# IREC-Sensor-PCB.net
KiCad netlist of a schematic drawn in EAGLE
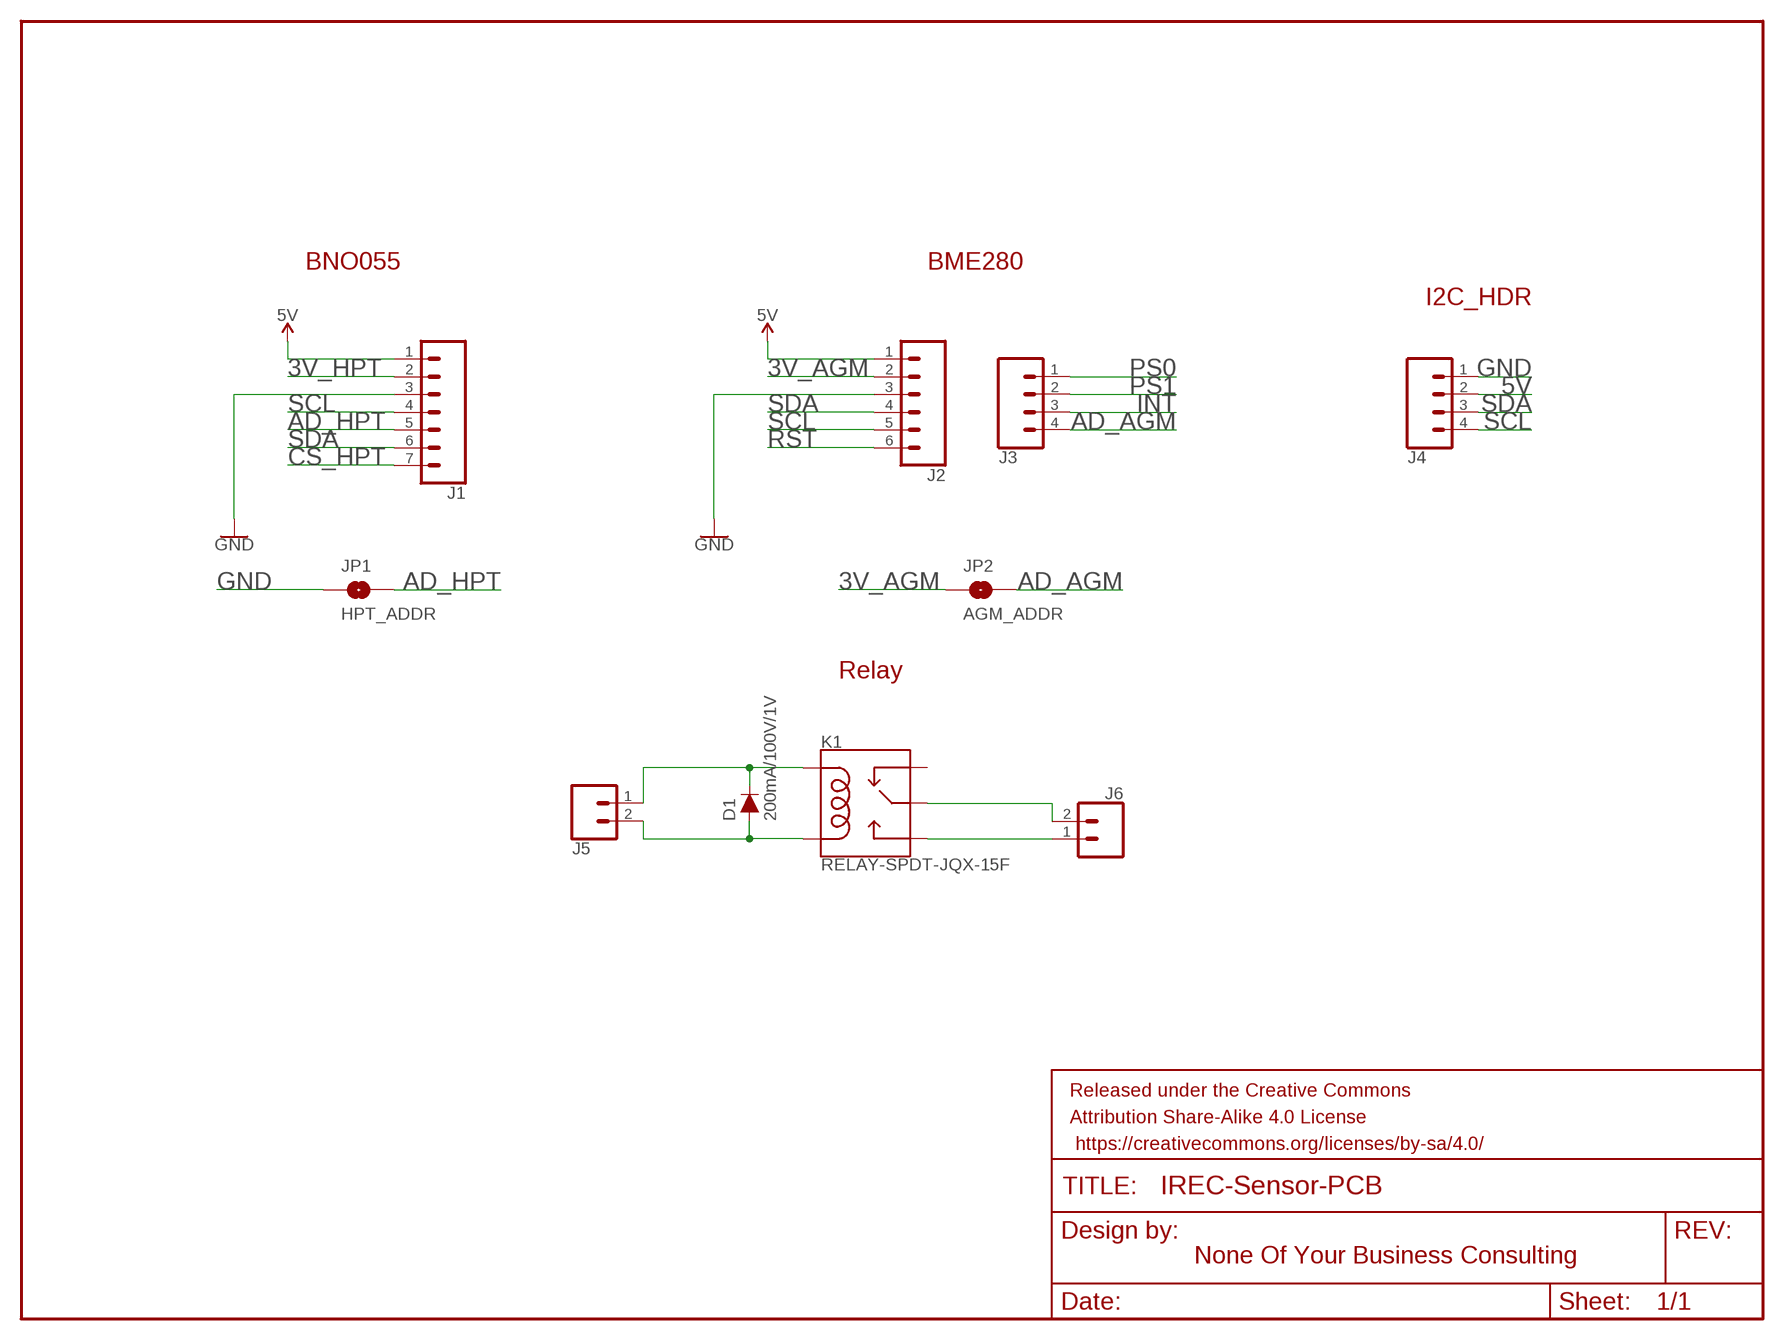
[diagram p0: schematic, sheet 1]

(export (version "E")
  (design (tool "Eeschema 10.0.6"))
  (components
    (comp (ref "D1")
      (value "200mA/100V/1V")
      (footprint "eagle-import:DIODE-1N4148")
      (libsource (lib "eagle-import") (part "DIODE-1N4148"))
    )
    (comp (ref "FRAME1")
      (value "FRAME-LETTER")
      (footprint "eagle-import:CREATIVE_COMMONS")
      (libsource (lib "eagle-import") (part "FRAME-LETTER"))
    )
    (comp (ref "J1")
      (value "CONN_07")
      (footprint "eagle-import:1X07")
      (libsource (lib "eagle-import") (part "CONN_07"))
    )
    (comp (ref "J2")
      (value "CONN_06SILK_FEMALE_PTH")
      (footprint "eagle-import:1X06")
      (libsource (lib "eagle-import") (part "CONN_06SILK_FEMALE_PTH"))
    )
    (comp (ref "J3")
      (value "CONN_04")
      (footprint "eagle-import:1X04")
      (libsource (lib "eagle-import") (part "CONN_04"))
    )
    (comp (ref "J4")
      (value "CONN_04SCREW")
      (footprint "eagle-import:SCREWTERMINAL-3.5MM-4")
      (libsource (lib "eagle-import") (part "CONN_04SCREW"))
    )
    (comp (ref "J5")
      (value "CONN_023.5MM")
      (footprint "eagle-import:SCREWTERMINAL-3.5MM-2")
      (libsource (lib "eagle-import") (part "CONN_023.5MM"))
    )
    (comp (ref "J6")
      (value "CONN_023.5MM")
      (footprint "eagle-import:SCREWTERMINAL-3.5MM-2")
      (libsource (lib "eagle-import") (part "CONN_023.5MM"))
    )
    (comp (ref "JP1")
      (value "HPT_ADDR")
      (footprint "eagle-import:SMT-JUMPER_2_NO_SILK")
      (libsource (lib "eagle-import") (part "JUMPER-SMT_2_NO_SILK"))
    )
    (comp (ref "JP2")
      (value "AGM_ADDR")
      (footprint "eagle-import:SMT-JUMPER_2_NO_SILK")
      (libsource (lib "eagle-import") (part "JUMPER-SMT_2_NO_SILK"))
    )
    (comp (ref "K1")
      (value "RELAY-SPDT-JQX-15F")
      (footprint "eagle-import:RELAY-T90")
      (libsource (lib "eagle-import") (part "RELAY-SPDT-JQX-15F"))
    )
  )
  (nets
    (net (code "1") (name "/3V_AGM") (class "Default")
      (node (ref "J2") (pin "2") (pinfunction "2_2") (pintype "passive"))
      (node (ref "JP2") (pin "1") (pinfunction "1_1") (pintype "passive"))
    )
    (net (code "2") (name "/3V_HPT") (class "Default")
      (node (ref "J1") (pin "2") (pinfunction "2_2") (pintype "passive"))
    )
    (net (code "3") (name "/AD_AGM") (class "Default")
      (node (ref "J3") (pin "4") (pinfunction "4_4") (pintype "passive"))
      (node (ref "JP2") (pin "2") (pinfunction "2_2") (pintype "passive"))
    )
    (net (code "4") (name "/AD_HPT") (class "Default")
      (node (ref "J1") (pin "5") (pinfunction "5_5") (pintype "passive"))
      (node (ref "JP1") (pin "2") (pinfunction "2_2") (pintype "passive"))
    )
    (net (code "5") (name "/CS_HPT") (class "Default")
      (node (ref "J1") (pin "7") (pinfunction "7_7") (pintype "passive"))
    )
    (net (code "6") (name "/INT") (class "Default")
      (node (ref "J3") (pin "3") (pinfunction "3_3") (pintype "passive"))
    )
    (net (code "7") (name "/PS0") (class "Default")
      (node (ref "J3") (pin "1") (pinfunction "1_1") (pintype "passive"))
    )
    (net (code "8") (name "/PS1") (class "Default")
      (node (ref "J3") (pin "2") (pinfunction "2_2") (pintype "passive"))
    )
    (net (code "9") (name "/RST") (class "Default")
      (node (ref "J2") (pin "6") (pinfunction "6_6") (pintype "passive"))
    )
    (net (code "10") (name "/SCL") (class "Default")
      (node (ref "J1") (pin "4") (pinfunction "4_4") (pintype "passive"))
      (node (ref "J2") (pin "5") (pinfunction "5_5") (pintype "passive"))
      (node (ref "J4") (pin "4") (pinfunction "4_4") (pintype "passive"))
    )
    (net (code "11") (name "/SDA") (class "Default")
      (node (ref "J1") (pin "6") (pinfunction "6_6") (pintype "passive"))
      (node (ref "J2") (pin "4") (pinfunction "4_4") (pintype "passive"))
      (node (ref "J4") (pin "3") (pinfunction "3_3") (pintype "passive"))
    )
    (net (code "12") (name "5V") (class "Default")
      (node (ref "J1") (pin "1") (pinfunction "1_1") (pintype "passive"))
      (node (ref "J2") (pin "1") (pinfunction "1_1") (pintype "passive"))
      (node (ref "J4") (pin "2") (pinfunction "2_2") (pintype "passive"))
    )
    (net (code "13") (name "GND") (class "Default")
      (node (ref "J1") (pin "3") (pinfunction "3_3") (pintype "passive"))
      (node (ref "J2") (pin "3") (pinfunction "3_3") (pintype "passive"))
      (node (ref "J4") (pin "1") (pinfunction "1_1") (pintype "passive"))
      (node (ref "JP1") (pin "1") (pinfunction "1_1") (pintype "passive"))
    )
    (net (code "14") (name "Net-(D1-PadA)") (class "Default")
      (node (ref "D1") (pin "A") (pinfunction "A_A") (pintype "passive"))
      (node (ref "J5") (pin "2") (pinfunction "2_2") (pintype "passive"))
      (node (ref "K1") (pin "COIL2") (pinfunction "COIL2_COIL2") (pintype "bidirectional"))
    )
    (net (code "15") (name "Net-(D1-PadC)") (class "Default")
      (node (ref "D1") (pin "C") (pinfunction "C_C") (pintype "passive"))
      (node (ref "J5") (pin "1") (pinfunction "1_1") (pintype "passive"))
      (node (ref "K1") (pin "COIL1") (pinfunction "COIL1_COIL1") (pintype "bidirectional"))
    )
    (net (code "16") (name "Net-(J6-Pad1)") (class "Default")
      (node (ref "J6") (pin "1") (pinfunction "1_1") (pintype "passive"))
      (node (ref "K1") (pin "NO") (pinfunction "NO_NO") (pintype "bidirectional"))
    )
    (net (code "17") (name "Net-(J6-Pad2)") (class "Default")
      (node (ref "J6") (pin "2") (pinfunction "2_2") (pintype "passive"))
      (node (ref "K1") (pin "MAIN") (pinfunction "MAIN_MAIN") (pintype "bidirectional"))
    )
    (net (code "18") (name "unconnected-(K1-PadNC)") (class "Default")
      (node (ref "K1") (pin "NC") (pinfunction "NC_NC") (pintype "bidirectional"))
    )
  )
)
